# HACKberry_SizeM_Right.net
KiCad netlist of a schematic drawn in EAGLE
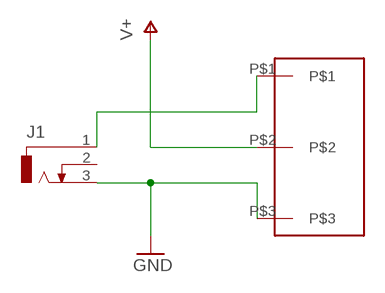
[diagram p0: schematic, sheet 1]
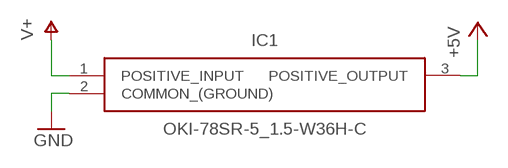
[diagram p1: schematic, sheet 2]
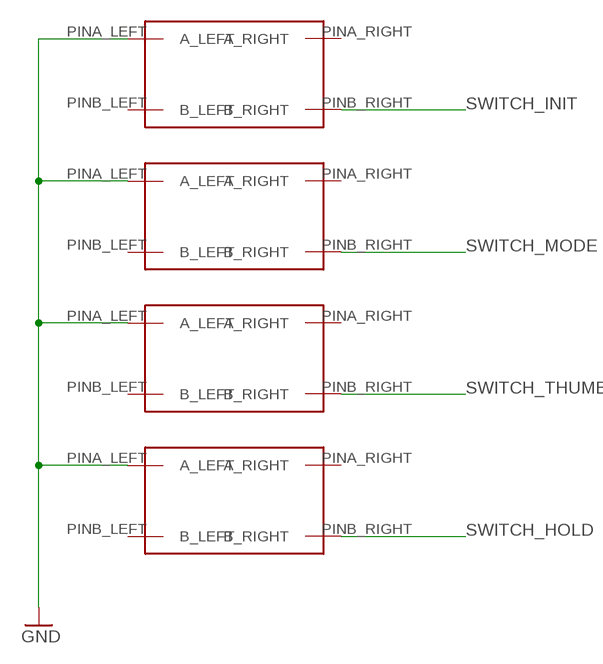
[diagram p2: schematic, sheet 3]
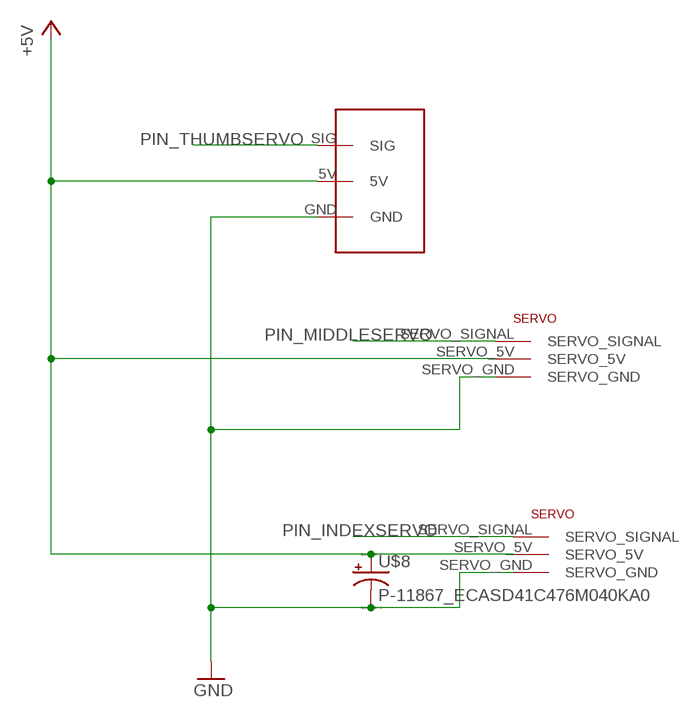
[diagram p3: schematic, sheet 4]
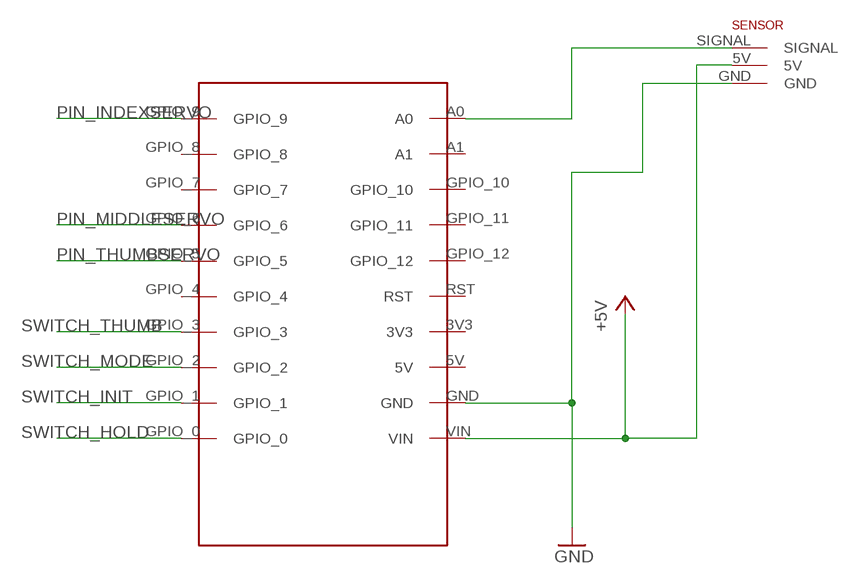
[diagram p4: schematic, sheet 5]

(export (version "E")
  (design (tool "Eeschema 10.0.6"))
  (components
    (comp (ref "IC1")
      (value "OKI-78SR-5_1.5-W36H-C")
      (footprint "eagle-import:OKI-78SR-HORIZONTAL")
      (fields
        (field (name "MANUFACTURER_PART_NUMBER") "OKI-78SR-5/1.5-W36H-C")
        (field (name "RS_PART_NUMBER") "7962138P")
      )
      (libsource (lib "eagle-import") (part "OKI-78SR-5_1.5-W36H-C"))
    )
    (comp (ref "INDEXPIN")
      (value "NN_SERVO")
      (footprint "eagle-import:NN_SERVO")
      (libsource (lib "eagle-import") (part "NN_SERVO"))
    )
    (comp (ref "MIDDLEPIN")
      (value "NN_SERVO")
      (footprint "eagle-import:NN_SERVO")
      (libsource (lib "eagle-import") (part "NN_SERVO"))
    )
    (comp (ref "THUMBPIN")
      (value "53047-0310_SERVO")
      (footprint "eagle-import:53047-0310_SERVO")
      (libsource (lib "eagle-import") (part "53047-0310_SERVO"))
    )
    (comp (ref "U$8")
      (value "P-11867_ECASD41C476M040KA0")
      (footprint "eagle-import:ECASD41C476M040KA0")
      (libsource (lib "eagle-import") (part "P-11867_ECASD41C476M040KA0"))
    )
    (comp (ref "J1")
      (value "DCJ0303")
      (footprint "eagle-import:DCJ0303")
      (libsource (lib "eagle-import") (part "DCJ0303"))
    )
    (comp (ref "U$2")
      (value "SS-12D00")
      (footprint "eagle-import:SS-12D00")
      (libsource (lib "eagle-import") (part "SS-12D00"))
    )
    (comp (ref "U$1")
      (value "SKRPACE010")
      (footprint "eagle-import:SKRPACE010")
      (libsource (lib "eagle-import") (part "SKRPACE010"))
    )
    (comp (ref "U$3")
      (value "SKRPACE010")
      (footprint "eagle-import:SKRPACE010")
      (libsource (lib "eagle-import") (part "SKRPACE010"))
    )
    (comp (ref "U$4")
      (value "SKRPACE010")
      (footprint "eagle-import:SKRPACE010")
      (libsource (lib "eagle-import") (part "SKRPACE010"))
    )
    (comp (ref "U$5")
      (value "SKRPACE010")
      (footprint "eagle-import:SKRPACE010")
      (libsource (lib "eagle-import") (part "SKRPACE010"))
    )
    (comp (ref "U$6")
      (value "POLOLU_A_STAR_32U4_MICRO")
      (footprint "eagle-import:POLOLU_A_STAR_32U4_MICRO")
      (libsource (lib "eagle-import") (part "POLOLU_A_STAR_32U4_MICRO"))
    )
    (comp (ref "U$7")
      (value "NN_SENSOR")
      (footprint "eagle-import:NN_SENSOR")
      (libsource (lib "eagle-import") (part "NN_SENSOR"))
    )
  )
  (nets
    (net (code "1") (name "+5V") (class "Default")
      (node (ref "IC1") (pin "3") (pinfunction "POSITIVE_OUTPUT_3") (pintype "output"))
      (node (ref "INDEXPIN") (pin "SERVO_5V") (pinfunction "SERVO_5V_SERVO_5V") (pintype "bidirectional"))
      (node (ref "MIDDLEPIN") (pin "SERVO_5V") (pinfunction "SERVO_5V_SERVO_5V") (pintype "bidirectional"))
      (node (ref "THUMBPIN") (pin "5V") (pinfunction "5V_5V") (pintype "bidirectional"))
      (node (ref "U$6") (pin "VIN") (pinfunction "VIN_VIN") (pintype "bidirectional"))
      (node (ref "U$7") (pin "5V") (pinfunction "5V_5V") (pintype "bidirectional"))
      (node (ref "U$8") (pin "+") (pinfunction "+_+") (pintype "passive"))
    )
    (net (code "2") (name "GND") (class "Default")
      (node (ref "IC1") (pin "2") (pinfunction "COMMON_(GROUND)_2") (pintype "passive"))
      (node (ref "INDEXPIN") (pin "SERVO_GND") (pinfunction "SERVO_GND_SERVO_GND") (pintype "bidirectional"))
      (node (ref "J1") (pin "3") (pinfunction "3_3") (pintype "passive"))
      (node (ref "MIDDLEPIN") (pin "SERVO_GND") (pinfunction "SERVO_GND_SERVO_GND") (pintype "bidirectional"))
      (node (ref "THUMBPIN") (pin "GND") (pinfunction "GND_GND") (pintype "bidirectional"))
      (node (ref "U$1") (pin "PINA_LEFT") (pinfunction "A_LEFT_PINA_LEFT") (pintype "bidirectional"))
      (node (ref "U$2") (pin "P$3") (pinfunction "P$3_P$3") (pintype "bidirectional"))
      (node (ref "U$3") (pin "PINA_LEFT") (pinfunction "A_LEFT_PINA_LEFT") (pintype "bidirectional"))
      (node (ref "U$4") (pin "PINA_LEFT") (pinfunction "A_LEFT_PINA_LEFT") (pintype "bidirectional"))
      (node (ref "U$5") (pin "PINA_LEFT") (pinfunction "A_LEFT_PINA_LEFT") (pintype "bidirectional"))
      (node (ref "U$6") (pin "GND") (pinfunction "GND_GND") (pintype "bidirectional"))
      (node (ref "U$7") (pin "GND") (pinfunction "GND_GND") (pintype "bidirectional"))
      (node (ref "U$8") (pin "-") (pinfunction "-_-") (pintype "passive"))
    )
    (net (code "3") (name "Net-(J1-Pad1)") (class "Default")
      (node (ref "J1") (pin "1") (pinfunction "1_1") (pintype "passive"))
      (node (ref "U$2") (pin "P$1") (pinfunction "P$1_P$1") (pintype "bidirectional"))
    )
    (net (code "4") (name "Net-(U$6-PadA0)") (class "Default")
      (node (ref "U$6") (pin "A0") (pinfunction "A0_A0") (pintype "bidirectional"))
      (node (ref "U$7") (pin "SIGNAL") (pinfunction "SIGNAL_SIGNAL") (pintype "bidirectional"))
    )
    (net (code "5") (name "PIN_INDEXSERVO") (class "Default")
      (node (ref "INDEXPIN") (pin "SERVO_SIGNAL") (pinfunction "SERVO_SIGNAL_SERVO_SIGNAL") (pintype "bidirectional"))
      (node (ref "U$6") (pin "GPIO_9") (pinfunction "GPIO_9_GPIO_9") (pintype "bidirectional"))
    )
    (net (code "6") (name "PIN_MIDDLESERVO") (class "Default")
      (node (ref "MIDDLEPIN") (pin "SERVO_SIGNAL") (pinfunction "SERVO_SIGNAL_SERVO_SIGNAL") (pintype "bidirectional"))
      (node (ref "U$6") (pin "GPIO_6") (pinfunction "GPIO_6_GPIO_6") (pintype "bidirectional"))
    )
    (net (code "7") (name "PIN_THUMBSERVO") (class "Default")
      (node (ref "THUMBPIN") (pin "SIG") (pinfunction "SIG_SIG") (pintype "bidirectional"))
      (node (ref "U$6") (pin "GPIO_5") (pinfunction "GPIO_5_GPIO_5") (pintype "bidirectional"))
    )
    (net (code "8") (name "SWITCH_HOLD") (class "Default")
      (node (ref "U$5") (pin "PINB_RIGHT") (pinfunction "B_RIGHT_PINB_RIGHT") (pintype "bidirectional"))
      (node (ref "U$6") (pin "GPIO_0") (pinfunction "GPIO_0_GPIO_0") (pintype "bidirectional"))
    )
    (net (code "9") (name "SWITCH_INIT") (class "Default")
      (node (ref "U$1") (pin "PINB_RIGHT") (pinfunction "B_RIGHT_PINB_RIGHT") (pintype "bidirectional"))
      (node (ref "U$6") (pin "GPIO_1") (pinfunction "GPIO_1_GPIO_1") (pintype "bidirectional"))
    )
    (net (code "10") (name "SWITCH_MODE") (class "Default")
      (node (ref "U$3") (pin "PINB_RIGHT") (pinfunction "B_RIGHT_PINB_RIGHT") (pintype "bidirectional"))
      (node (ref "U$6") (pin "GPIO_2") (pinfunction "GPIO_2_GPIO_2") (pintype "bidirectional"))
    )
    (net (code "11") (name "SWITCH_THUMB") (class "Default")
      (node (ref "U$4") (pin "PINB_RIGHT") (pinfunction "B_RIGHT_PINB_RIGHT") (pintype "bidirectional"))
      (node (ref "U$6") (pin "GPIO_3") (pinfunction "GPIO_3_GPIO_3") (pintype "bidirectional"))
    )
    (net (code "12") (name "V+") (class "Default")
      (node (ref "IC1") (pin "1") (pinfunction "POSITIVE_INPUT_1") (pintype "input"))
      (node (ref "U$2") (pin "P$2") (pinfunction "P$2_P$2") (pintype "bidirectional"))
    )
    (net (code "13") (name "unconnected-(J1-Pad2)") (class "Default")
      (node (ref "J1") (pin "2") (pinfunction "2_2") (pintype "passive"))
    )
    (net (code "14") (name "unconnected-(U$1-A_RIGHT-PadPINA_RIGHT)") (class "Default")
      (node (ref "U$1") (pin "PINA_RIGHT") (pinfunction "A_RIGHT_PINA_RIGHT") (pintype "bidirectional"))
    )
    (net (code "15") (name "unconnected-(U$1-B_LEFT-PadPINB_LEFT)") (class "Default")
      (node (ref "U$1") (pin "PINB_LEFT") (pinfunction "B_LEFT_PINB_LEFT") (pintype "bidirectional"))
    )
    (net (code "16") (name "unconnected-(U$3-A_RIGHT-PadPINA_RIGHT)") (class "Default")
      (node (ref "U$3") (pin "PINA_RIGHT") (pinfunction "A_RIGHT_PINA_RIGHT") (pintype "bidirectional"))
    )
    (net (code "17") (name "unconnected-(U$3-B_LEFT-PadPINB_LEFT)") (class "Default")
      (node (ref "U$3") (pin "PINB_LEFT") (pinfunction "B_LEFT_PINB_LEFT") (pintype "bidirectional"))
    )
    (net (code "18") (name "unconnected-(U$4-A_RIGHT-PadPINA_RIGHT)") (class "Default")
      (node (ref "U$4") (pin "PINA_RIGHT") (pinfunction "A_RIGHT_PINA_RIGHT") (pintype "bidirectional"))
    )
    (net (code "19") (name "unconnected-(U$4-B_LEFT-PadPINB_LEFT)") (class "Default")
      (node (ref "U$4") (pin "PINB_LEFT") (pinfunction "B_LEFT_PINB_LEFT") (pintype "bidirectional"))
    )
    (net (code "20") (name "unconnected-(U$5-A_RIGHT-PadPINA_RIGHT)") (class "Default")
      (node (ref "U$5") (pin "PINA_RIGHT") (pinfunction "A_RIGHT_PINA_RIGHT") (pintype "bidirectional"))
    )
    (net (code "21") (name "unconnected-(U$5-B_LEFT-PadPINB_LEFT)") (class "Default")
      (node (ref "U$5") (pin "PINB_LEFT") (pinfunction "B_LEFT_PINB_LEFT") (pintype "bidirectional"))
    )
    (net (code "22") (name "unconnected-(U$6-Pad3V3)") (class "Default")
      (node (ref "U$6") (pin "3V3") (pinfunction "3V3_3V3") (pintype "bidirectional"))
    )
    (net (code "23") (name "unconnected-(U$6-Pad5V)") (class "Default")
      (node (ref "U$6") (pin "5V") (pinfunction "5V_5V") (pintype "bidirectional"))
    )
    (net (code "24") (name "unconnected-(U$6-PadA1)") (class "Default")
      (node (ref "U$6") (pin "A1") (pinfunction "A1_A1") (pintype "bidirectional"))
    )
    (net (code "25") (name "unconnected-(U$6-PadGPIO_4)") (class "Default")
      (node (ref "U$6") (pin "GPIO_4") (pinfunction "GPIO_4_GPIO_4") (pintype "bidirectional"))
    )
    (net (code "26") (name "unconnected-(U$6-PadGPIO_7)") (class "Default")
      (node (ref "U$6") (pin "GPIO_7") (pinfunction "GPIO_7_GPIO_7") (pintype "bidirectional"))
    )
    (net (code "27") (name "unconnected-(U$6-PadGPIO_8)") (class "Default")
      (node (ref "U$6") (pin "GPIO_8") (pinfunction "GPIO_8_GPIO_8") (pintype "bidirectional"))
    )
    (net (code "28") (name "unconnected-(U$6-PadGPIO_10)") (class "Default")
      (node (ref "U$6") (pin "GPIO_10") (pinfunction "GPIO_10_GPIO_10") (pintype "bidirectional"))
    )
    (net (code "29") (name "unconnected-(U$6-PadGPIO_11)") (class "Default")
      (node (ref "U$6") (pin "GPIO_11") (pinfunction "GPIO_11_GPIO_11") (pintype "bidirectional"))
    )
    (net (code "30") (name "unconnected-(U$6-PadGPIO_12)") (class "Default")
      (node (ref "U$6") (pin "GPIO_12") (pinfunction "GPIO_12_GPIO_12") (pintype "bidirectional"))
    )
    (net (code "31") (name "unconnected-(U$6-PadRST)") (class "Default")
      (node (ref "U$6") (pin "RST") (pinfunction "RST_RST") (pintype "bidirectional"))
    )
  )
)
